# board.net
KiCad netlist of a schematic drawn in EAGLE
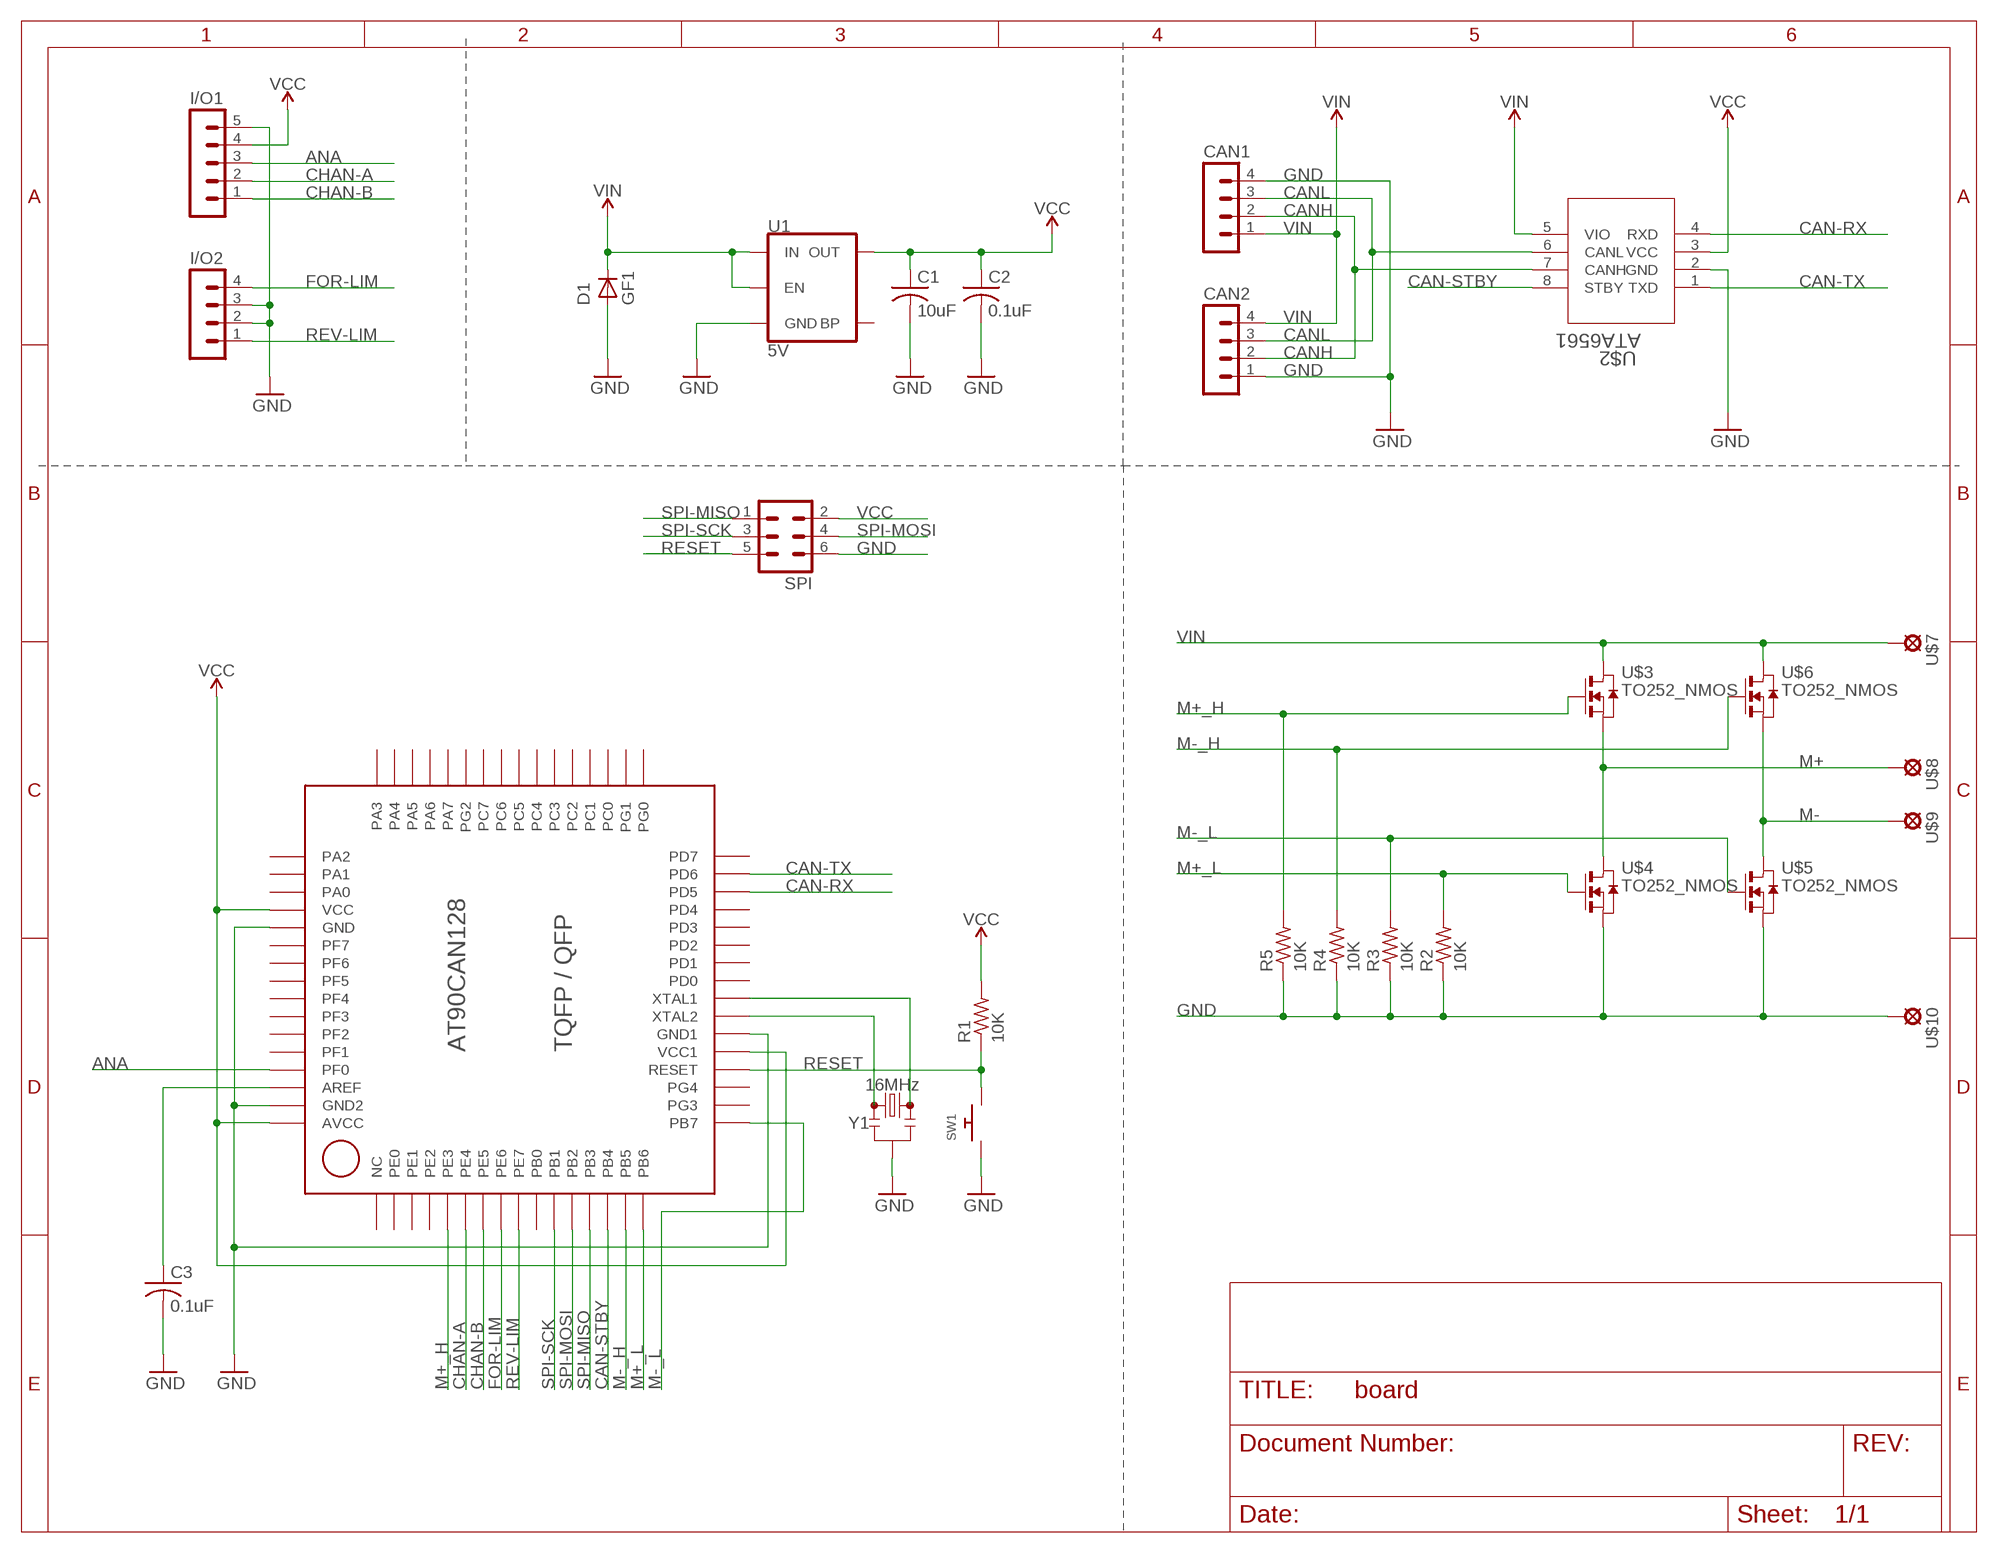
[diagram p0: schematic, sheet 1]

(export (version "E")
  (design (tool "Eeschema 10.0.6"))
  (components
    (comp (ref "C1")
      (value "10uF")
      (footprint "eagle-import:C0603")
      (libsource (lib "eagle-import") (part "C-USC0603"))
    )
    (comp (ref "C2")
      (value "0.1uF")
      (footprint "eagle-import:C0603")
      (libsource (lib "eagle-import") (part "C-USC0603"))
    )
    (comp (ref "C3")
      (value "0.1uF")
      (footprint "eagle-import:C0603")
      (libsource (lib "eagle-import") (part "C-USC0603"))
    )
    (comp (ref "CAN1")
      (value "MA04-1")
      (footprint "eagle-import:MA04-1")
      (libsource (lib "eagle-import") (part "MA04-1"))
    )
    (comp (ref "CAN2")
      (value "MA04-1")
      (footprint "eagle-import:MA04-1")
      (libsource (lib "eagle-import") (part "MA04-1"))
    )
    (comp (ref "D1")
      (value "GF1")
      (footprint "eagle-import:SMA-DO214AC")
      (libsource (lib "eagle-import") (part "GF1"))
    )
    (comp (ref "I/O1")
      (value "MA05-1")
      (footprint "eagle-import:MA05-1")
      (libsource (lib "eagle-import") (part "MA05-1"))
    )
    (comp (ref "I/O2")
      (value "MA04-1")
      (footprint "eagle-import:MA04-1")
      (libsource (lib "eagle-import") (part "MA04-1"))
    )
    (comp (ref "R1")
      (value "10K")
      (footprint "eagle-import:R0603")
      (libsource (lib "eagle-import") (part "R-US_R0603"))
    )
    (comp (ref "R2")
      (value "10K")
      (footprint "eagle-import:R0603")
      (libsource (lib "eagle-import") (part "R-US_R0603"))
    )
    (comp (ref "R3")
      (value "10K")
      (footprint "eagle-import:R0603")
      (libsource (lib "eagle-import") (part "R-US_R0603"))
    )
    (comp (ref "R4")
      (value "10K")
      (footprint "eagle-import:R0603")
      (libsource (lib "eagle-import") (part "R-US_R0603"))
    )
    (comp (ref "R5")
      (value "10K")
      (footprint "eagle-import:R0603")
      (libsource (lib "eagle-import") (part "R-US_R0603"))
    )
    (comp (ref "SPI")
      (value "MA03-2")
      (footprint "eagle-import:MA03-2")
      (libsource (lib "eagle-import") (part "MA03-2"))
    )
    (comp (ref "SW1")
      (value "SWITCH_PUSHBUTTONEVQ-PE")
      (footprint "eagle-import:TACT_PANA-EVQ")
      (libsource (lib "eagle-import") (part "SWITCH_PUSHBUTTONEVQ-PE"))
    )
    (comp (ref "U$1")
      (value "AT90CAN128")
      (footprint "eagle-import:QFP64_TQFP64")
      (libsource (lib "eagle-import") (part "AT90CAN128"))
    )
    (comp (ref "U$2")
      (value "ATA6561")
      (footprint "eagle-import:SO8")
      (libsource (lib "eagle-import") (part "ATA6561"))
    )
    (comp (ref "U$3")
      (value "TO252_NMOS")
      (footprint "eagle-import:TO252")
      (libsource (lib "eagle-import") (part "TO252_NMOS"))
    )
    (comp (ref "U$4")
      (value "TO252_NMOS")
      (footprint "eagle-import:TO252")
      (libsource (lib "eagle-import") (part "TO252_NMOS"))
    )
    (comp (ref "U$5")
      (value "TO252_NMOS")
      (footprint "eagle-import:TO252")
      (libsource (lib "eagle-import") (part "TO252_NMOS"))
    )
    (comp (ref "U$6")
      (value "TO252_NMOS")
      (footprint "eagle-import:TO252")
      (libsource (lib "eagle-import") (part "TO252_NMOS"))
    )
    (comp (ref "U$7")
      (value "SOLPAD")
      (footprint "eagle-import:SOLPAD")
      (libsource (lib "eagle-import") (part "SOLPAD"))
    )
    (comp (ref "U$8")
      (value "SOLPAD")
      (footprint "eagle-import:SOLPAD")
      (libsource (lib "eagle-import") (part "SOLPAD"))
    )
    (comp (ref "U$9")
      (value "SOLPAD")
      (footprint "eagle-import:SOLPAD")
      (libsource (lib "eagle-import") (part "SOLPAD"))
    )
    (comp (ref "U$10")
      (value "SOLPAD")
      (footprint "eagle-import:SOLPAD")
      (libsource (lib "eagle-import") (part "SOLPAD"))
    )
    (comp (ref "U1")
      (value "5V")
      (footprint "eagle-import:SOT23-5")
      (libsource (lib "eagle-import") (part "V_REG_MIC52055V"))
    )
    (comp (ref "Y1")
      (value "16MHz")
      (footprint "eagle-import:RESONATOR-SMD-3.2X1.3")
      (libsource (lib "eagle-import") (part "RESONATOR-16MHZSMD_3.2X1.3"))
    )
  )
  (nets
    (net (code "1") (name "/ANA") (class "Default")
      (node (ref "I/O1") (pin "3") (pinfunction "3_3") (pintype "passive"))
      (node (ref "U$1") (pin "61") (pinfunction "PF0_61") (pintype "bidirectional"))
    )
    (net (code "2") (name "/CAN-RX") (class "Default")
      (node (ref "U$1") (pin "30") (pinfunction "PD5_30") (pintype "bidirectional"))
      (node (ref "U$2") (pin "4") (pinfunction "RXD_4") (pintype "input"))
    )
    (net (code "3") (name "/CAN-STBY") (class "Default")
      (node (ref "U$1") (pin "14") (pinfunction "PB4_14") (pintype "bidirectional"))
      (node (ref "U$2") (pin "8") (pinfunction "STBY_8") (pintype "passive"))
    )
    (net (code "4") (name "/CAN-TX") (class "Default")
      (node (ref "U$1") (pin "31") (pinfunction "PD6_31") (pintype "bidirectional"))
      (node (ref "U$2") (pin "1") (pinfunction "TXD_1") (pintype "power_in"))
    )
    (net (code "5") (name "/CANH") (class "Default")
      (node (ref "CAN1") (pin "2") (pinfunction "2_2") (pintype "passive"))
      (node (ref "CAN2") (pin "2") (pinfunction "2_2") (pintype "passive"))
      (node (ref "U$2") (pin "7") (pinfunction "CANH_7") (pintype "output"))
    )
    (net (code "6") (name "/CANL") (class "Default")
      (node (ref "CAN1") (pin "3") (pinfunction "3_3") (pintype "passive"))
      (node (ref "CAN2") (pin "3") (pinfunction "3_3") (pintype "passive"))
      (node (ref "U$2") (pin "6") (pinfunction "CANL_6") (pintype "output"))
    )
    (net (code "7") (name "/CHAN-A") (class "Default")
      (node (ref "I/O1") (pin "2") (pinfunction "2_2") (pintype "passive"))
      (node (ref "U$1") (pin "6") (pinfunction "PE4_6") (pintype "bidirectional"))
    )
    (net (code "8") (name "/CHAN-B") (class "Default")
      (node (ref "I/O1") (pin "1") (pinfunction "1_1") (pintype "passive"))
      (node (ref "U$1") (pin "7") (pinfunction "PE5_7") (pintype "bidirectional"))
    )
    (net (code "9") (name "/FOR-LIM") (class "Default")
      (node (ref "I/O2") (pin "4") (pinfunction "4_4") (pintype "passive"))
      (node (ref "U$1") (pin "8") (pinfunction "PE6_8") (pintype "bidirectional"))
    )
    (net (code "10") (name "/M+") (class "Default")
      (node (ref "U$3") (pin "2") (pinfunction "S_2") (pintype "passive"))
      (node (ref "U$4") (pin "3") (pinfunction "D_3") (pintype "passive"))
      (node (ref "U$8") (pin "P$1") (pinfunction "MP_P$1") (pintype "passive"))
    )
    (net (code "11") (name "/M+_H") (class "Default")
      (node (ref "R5") (pin "2") (pinfunction "2_2") (pintype "passive"))
      (node (ref "U$1") (pin "5") (pinfunction "PE3_5") (pintype "bidirectional"))
      (node (ref "U$3") (pin "1") (pinfunction "G_1") (pintype "passive"))
    )
    (net (code "12") (name "/M+_L") (class "Default")
      (node (ref "R2") (pin "2") (pinfunction "2_2") (pintype "passive"))
      (node (ref "U$1") (pin "16") (pinfunction "PB6_16") (pintype "bidirectional"))
      (node (ref "U$4") (pin "1") (pinfunction "G_1") (pintype "passive"))
    )
    (net (code "13") (name "/M-") (class "Default")
      (node (ref "U$5") (pin "3") (pinfunction "D_3") (pintype "passive"))
      (node (ref "U$6") (pin "2") (pinfunction "S_2") (pintype "passive"))
      (node (ref "U$9") (pin "P$1") (pinfunction "MP_P$1") (pintype "passive"))
    )
    (net (code "14") (name "/M-_H") (class "Default")
      (node (ref "R4") (pin "2") (pinfunction "2_2") (pintype "passive"))
      (node (ref "U$1") (pin "15") (pinfunction "PB5_15") (pintype "bidirectional"))
      (node (ref "U$6") (pin "1") (pinfunction "G_1") (pintype "passive"))
    )
    (net (code "15") (name "/M-_L") (class "Default")
      (node (ref "R3") (pin "2") (pinfunction "2_2") (pintype "passive"))
      (node (ref "U$1") (pin "17") (pinfunction "PB7_17") (pintype "bidirectional"))
      (node (ref "U$5") (pin "1") (pinfunction "G_1") (pintype "passive"))
    )
    (net (code "16") (name "/RESET") (class "Default")
      (node (ref "R1") (pin "1") (pinfunction "1_1") (pintype "passive"))
      (node (ref "SPI") (pin "5") (pinfunction "5_5") (pintype "passive"))
      (node (ref "SW1") (pin "P$2") (pinfunction "P$2_P$2") (pintype "passive"))
      (node (ref "U$1") (pin "20") (pinfunction "RESET_20") (pintype "bidirectional"))
    )
    (net (code "17") (name "/REV-LIM") (class "Default")
      (node (ref "I/O2") (pin "1") (pinfunction "1_1") (pintype "passive"))
      (node (ref "U$1") (pin "9") (pinfunction "PE7_9") (pintype "bidirectional"))
    )
    (net (code "18") (name "/SPI-MISO") (class "Default")
      (node (ref "SPI") (pin "1") (pinfunction "1_1") (pintype "passive"))
      (node (ref "U$1") (pin "13") (pinfunction "PB3_13") (pintype "bidirectional"))
    )
    (net (code "19") (name "/SPI-MOSI") (class "Default")
      (node (ref "SPI") (pin "4") (pinfunction "4_4") (pintype "passive"))
      (node (ref "U$1") (pin "12") (pinfunction "PB2_12") (pintype "bidirectional"))
    )
    (net (code "20") (name "/SPI-SCK") (class "Default")
      (node (ref "SPI") (pin "3") (pinfunction "3_3") (pintype "passive"))
      (node (ref "U$1") (pin "11") (pinfunction "PB1_11") (pintype "bidirectional"))
    )
    (net (code "21") (name "GND") (class "Default")
      (node (ref "C1") (pin "2") (pinfunction "2_2") (pintype "passive"))
      (node (ref "C2") (pin "2") (pinfunction "2_2") (pintype "passive"))
      (node (ref "C3") (pin "2") (pinfunction "2_2") (pintype "passive"))
      (node (ref "CAN1") (pin "4") (pinfunction "4_4") (pintype "passive"))
      (node (ref "CAN2") (pin "1") (pinfunction "1_1") (pintype "passive"))
      (node (ref "D1") (pin "A") (pinfunction "A_A") (pintype "passive"))
      (node (ref "I/O1") (pin "5") (pinfunction "5_5") (pintype "passive"))
      (node (ref "I/O2") (pin "2") (pinfunction "2_2") (pintype "passive"))
      (node (ref "I/O2") (pin "3") (pinfunction "3_3") (pintype "passive"))
      (node (ref "R2") (pin "1") (pinfunction "1_1") (pintype "passive"))
      (node (ref "R3") (pin "1") (pinfunction "1_1") (pintype "passive"))
      (node (ref "R4") (pin "1") (pinfunction "1_1") (pintype "passive"))
      (node (ref "R5") (pin "1") (pinfunction "1_1") (pintype "passive"))
      (node (ref "SPI") (pin "6") (pinfunction "6_6") (pintype "passive"))
      (node (ref "SW1") (pin "P$1") (pinfunction "P$1_P$1") (pintype "passive"))
      (node (ref "U$1") (pin "22") (pinfunction "GND1_22") (pintype "bidirectional"))
      (node (ref "U$1") (pin "53") (pinfunction "GND_53") (pintype "bidirectional"))
      (node (ref "U$1") (pin "63") (pinfunction "GND2_63") (pintype "bidirectional"))
      (node (ref "U$10") (pin "P$1") (pinfunction "MP_P$1") (pintype "passive"))
      (node (ref "U$2") (pin "2") (pinfunction "GND_2") (pintype "input"))
      (node (ref "U$4") (pin "2") (pinfunction "S_2") (pintype "passive"))
      (node (ref "U$5") (pin "2") (pinfunction "S_2") (pintype "passive"))
      (node (ref "U1") (pin "2") (pinfunction "GND_2") (pintype "input"))
      (node (ref "Y1") (pin "2") (pinfunction "2_2") (pintype "passive"))
    )
    (net (code "22") (name "Net-(U$1-AREF)") (class "Default")
      (node (ref "C3") (pin "1") (pinfunction "1_1") (pintype "passive"))
      (node (ref "U$1") (pin "62") (pinfunction "AREF_62") (pintype "bidirectional"))
    )
    (net (code "23") (name "Net-(U$1-XTAL1)") (class "Default")
      (node (ref "U$1") (pin "24") (pinfunction "XTAL1_24") (pintype "bidirectional"))
      (node (ref "Y1") (pin "3") (pinfunction "3_3") (pintype "passive"))
    )
    (net (code "24") (name "Net-(U$1-XTAL2)") (class "Default")
      (node (ref "U$1") (pin "23") (pinfunction "XTAL2_23") (pintype "bidirectional"))
      (node (ref "Y1") (pin "1") (pinfunction "1_1") (pintype "passive"))
    )
    (net (code "25") (name "VCC") (class "Default")
      (node (ref "C1") (pin "1") (pinfunction "1_1") (pintype "passive"))
      (node (ref "C2") (pin "1") (pinfunction "1_1") (pintype "passive"))
      (node (ref "I/O1") (pin "4") (pinfunction "4_4") (pintype "passive"))
      (node (ref "R1") (pin "2") (pinfunction "2_2") (pintype "passive"))
      (node (ref "SPI") (pin "2") (pinfunction "2_2") (pintype "passive"))
      (node (ref "U$1") (pin "21") (pinfunction "VCC1_21") (pintype "bidirectional"))
      (node (ref "U$1") (pin "52") (pinfunction "VCC_52") (pintype "bidirectional"))
      (node (ref "U$1") (pin "64") (pinfunction "AVCC_64") (pintype "bidirectional"))
      (node (ref "U$2") (pin "3") (pinfunction "VCC_3") (pintype "input"))
      (node (ref "U1") (pin "5") (pinfunction "OUT_5") (pintype "passive"))
    )
    (net (code "26") (name "VIN") (class "Default")
      (node (ref "CAN1") (pin "1") (pinfunction "1_1") (pintype "passive"))
      (node (ref "CAN2") (pin "4") (pinfunction "4_4") (pintype "passive"))
      (node (ref "D1") (pin "K") (pinfunction "C_K") (pintype "passive"))
      (node (ref "U$2") (pin "5") (pinfunction "VIO_5") (pintype "passive"))
      (node (ref "U$3") (pin "3") (pinfunction "D_3") (pintype "passive"))
      (node (ref "U$6") (pin "3") (pinfunction "D_3") (pintype "passive"))
      (node (ref "U$7") (pin "P$1") (pinfunction "MP_P$1") (pintype "passive"))
      (node (ref "U1") (pin "1") (pinfunction "IN_1") (pintype "input"))
      (node (ref "U1") (pin "3") (pinfunction "EN_3") (pintype "input"))
    )
    (net (code "27") (name "unconnected-(U$1-NC-Pad1)") (class "Default")
      (node (ref "U$1") (pin "1") (pinfunction "NC_1") (pintype "bidirectional"))
    )
    (net (code "28") (name "unconnected-(U$1-PA0-Pad51)") (class "Default")
      (node (ref "U$1") (pin "51") (pinfunction "PA0_51") (pintype "bidirectional"))
    )
    (net (code "29") (name "unconnected-(U$1-PA1-Pad50)") (class "Default")
      (node (ref "U$1") (pin "50") (pinfunction "PA1_50") (pintype "bidirectional"))
    )
    (net (code "30") (name "unconnected-(U$1-PA2-Pad49)") (class "Default")
      (node (ref "U$1") (pin "49") (pinfunction "PA2_49") (pintype "bidirectional"))
    )
    (net (code "31") (name "unconnected-(U$1-PA3-Pad48)") (class "Default")
      (node (ref "U$1") (pin "48") (pinfunction "PA3_48") (pintype "bidirectional"))
    )
    (net (code "32") (name "unconnected-(U$1-PA4-Pad47)") (class "Default")
      (node (ref "U$1") (pin "47") (pinfunction "PA4_47") (pintype "bidirectional"))
    )
    (net (code "33") (name "unconnected-(U$1-PA5-Pad46)") (class "Default")
      (node (ref "U$1") (pin "46") (pinfunction "PA5_46") (pintype "bidirectional"))
    )
    (net (code "34") (name "unconnected-(U$1-PA6-Pad45)") (class "Default")
      (node (ref "U$1") (pin "45") (pinfunction "PA6_45") (pintype "bidirectional"))
    )
    (net (code "35") (name "unconnected-(U$1-PA7-Pad44)") (class "Default")
      (node (ref "U$1") (pin "44") (pinfunction "PA7_44") (pintype "bidirectional"))
    )
    (net (code "36") (name "unconnected-(U$1-PB0-Pad10)") (class "Default")
      (node (ref "U$1") (pin "10") (pinfunction "PB0_10") (pintype "bidirectional"))
    )
    (net (code "37") (name "unconnected-(U$1-PC0-Pad35)") (class "Default")
      (node (ref "U$1") (pin "35") (pinfunction "PC0_35") (pintype "bidirectional"))
    )
    (net (code "38") (name "unconnected-(U$1-PC1-Pad36)") (class "Default")
      (node (ref "U$1") (pin "36") (pinfunction "PC1_36") (pintype "bidirectional"))
    )
    (net (code "39") (name "unconnected-(U$1-PC2-Pad37)") (class "Default")
      (node (ref "U$1") (pin "37") (pinfunction "PC2_37") (pintype "bidirectional"))
    )
    (net (code "40") (name "unconnected-(U$1-PC3-Pad38)") (class "Default")
      (node (ref "U$1") (pin "38") (pinfunction "PC3_38") (pintype "bidirectional"))
    )
    (net (code "41") (name "unconnected-(U$1-PC4-Pad39)") (class "Default")
      (node (ref "U$1") (pin "39") (pinfunction "PC4_39") (pintype "bidirectional"))
    )
    (net (code "42") (name "unconnected-(U$1-PC5-Pad40)") (class "Default")
      (node (ref "U$1") (pin "40") (pinfunction "PC5_40") (pintype "bidirectional"))
    )
    (net (code "43") (name "unconnected-(U$1-PC6-Pad41)") (class "Default")
      (node (ref "U$1") (pin "41") (pinfunction "PC6_41") (pintype "bidirectional"))
    )
    (net (code "44") (name "unconnected-(U$1-PC7-Pad42)") (class "Default")
      (node (ref "U$1") (pin "42") (pinfunction "PC7_42") (pintype "bidirectional"))
    )
    (net (code "45") (name "unconnected-(U$1-PD0-Pad25)") (class "Default")
      (node (ref "U$1") (pin "25") (pinfunction "PD0_25") (pintype "bidirectional"))
    )
    (net (code "46") (name "unconnected-(U$1-PD1-Pad26)") (class "Default")
      (node (ref "U$1") (pin "26") (pinfunction "PD1_26") (pintype "bidirectional"))
    )
    (net (code "47") (name "unconnected-(U$1-PD2-Pad27)") (class "Default")
      (node (ref "U$1") (pin "27") (pinfunction "PD2_27") (pintype "bidirectional"))
    )
    (net (code "48") (name "unconnected-(U$1-PD3-Pad28)") (class "Default")
      (node (ref "U$1") (pin "28") (pinfunction "PD3_28") (pintype "bidirectional"))
    )
    (net (code "49") (name "unconnected-(U$1-PD4-Pad29)") (class "Default")
      (node (ref "U$1") (pin "29") (pinfunction "PD4_29") (pintype "bidirectional"))
    )
    (net (code "50") (name "unconnected-(U$1-PD7-Pad32)") (class "Default")
      (node (ref "U$1") (pin "32") (pinfunction "PD7_32") (pintype "bidirectional"))
    )
    (net (code "51") (name "unconnected-(U$1-PE0-Pad2)") (class "Default")
      (node (ref "U$1") (pin "2") (pinfunction "PE0_2") (pintype "bidirectional"))
    )
    (net (code "52") (name "unconnected-(U$1-PE1-Pad3)") (class "Default")
      (node (ref "U$1") (pin "3") (pinfunction "PE1_3") (pintype "bidirectional"))
    )
    (net (code "53") (name "unconnected-(U$1-PE2-Pad4)") (class "Default")
      (node (ref "U$1") (pin "4") (pinfunction "PE2_4") (pintype "bidirectional"))
    )
    (net (code "54") (name "unconnected-(U$1-PF1-Pad60)") (class "Default")
      (node (ref "U$1") (pin "60") (pinfunction "PF1_60") (pintype "bidirectional"))
    )
    (net (code "55") (name "unconnected-(U$1-PF2-Pad59)") (class "Default")
      (node (ref "U$1") (pin "59") (pinfunction "PF2_59") (pintype "bidirectional"))
    )
    (net (code "56") (name "unconnected-(U$1-PF3-Pad58)") (class "Default")
      (node (ref "U$1") (pin "58") (pinfunction "PF3_58") (pintype "bidirectional"))
    )
    (net (code "57") (name "unconnected-(U$1-PF4-Pad57)") (class "Default")
      (node (ref "U$1") (pin "57") (pinfunction "PF4_57") (pintype "bidirectional"))
    )
    (net (code "58") (name "unconnected-(U$1-PF5-Pad56)") (class "Default")
      (node (ref "U$1") (pin "56") (pinfunction "PF5_56") (pintype "bidirectional"))
    )
    (net (code "59") (name "unconnected-(U$1-PF6-Pad55)") (class "Default")
      (node (ref "U$1") (pin "55") (pinfunction "PF6_55") (pintype "bidirectional"))
    )
    (net (code "60") (name "unconnected-(U$1-PF7-Pad54)") (class "Default")
      (node (ref "U$1") (pin "54") (pinfunction "PF7_54") (pintype "bidirectional"))
    )
    (net (code "61") (name "unconnected-(U$1-PG0-Pad33)") (class "Default")
      (node (ref "U$1") (pin "33") (pinfunction "PG0_33") (pintype "bidirectional"))
    )
    (net (code "62") (name "unconnected-(U$1-PG1-Pad34)") (class "Default")
      (node (ref "U$1") (pin "34") (pinfunction "PG1_34") (pintype "bidirectional"))
    )
    (net (code "63") (name "unconnected-(U$1-PG2-Pad43)") (class "Default")
      (node (ref "U$1") (pin "43") (pinfunction "PG2_43") (pintype "bidirectional"))
    )
    (net (code "64") (name "unconnected-(U$1-PG3-Pad18)") (class "Default")
      (node (ref "U$1") (pin "18") (pinfunction "PG3_18") (pintype "bidirectional"))
    )
    (net (code "65") (name "unconnected-(U$1-PG4-Pad19)") (class "Default")
      (node (ref "U$1") (pin "19") (pinfunction "PG4_19") (pintype "bidirectional"))
    )
    (net (code "66") (name "unconnected-(U1-BP-Pad4)") (class "Default")
      (node (ref "U1") (pin "4") (pinfunction "BP_4") (pintype "input"))
    )
  )
)
